# LED_Driver.net
KiCad netlist of a schematic drawn in Altium Designer
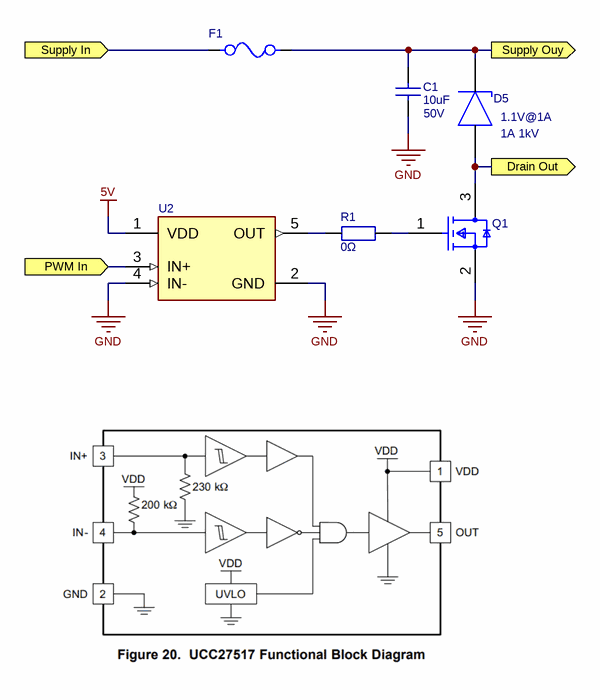
[diagram p0: LED Driver.SchDoc]

(export (version "E")
  (design (tool "Eeschema 10.0.6"))
  (components
    (comp (ref "C1")
      (value "10uF")
      (footprint "CAPC3225X20N")
      (fields (field (name "RATING") "50V"))
      (libsource (lib "SchematicLibrary") (part "SMD_Cap"))
    )
    (comp (ref "D5")
      (value "1.1V@1A")
      (footprint "sod-123FL")
      (description "1A Independent Type 1kV 1.1V@1A SOD-123FL Diodes")
      (fields (field (name "MPN") "SM4007PL") (field (name "RATING") "1A 1kV"))
      (libsource (lib "Miscellaneous Devices") (part "d386f69c7d770905792c16b93fa31a7"))
    )
    (comp (ref "F1")
      (value "~")
      (footprint "FP-0685T-IPC_C")
      (description "FUSE 3.0A 63VAC/DC SLOW 1206")
      (fields (field (name "MPN") "0468003.NRHF"))
      (libsource (lib "Altium Content Vault") (part "5bcf9b9f640e542cf0359d10258e979"))
    )
    (comp (ref "Q1")
      (value "~")
      (footprint "SOT95P245X110-3N")
      (description "N-Channel 30V 5.7A 1.5V @ 250uA 26.5mΩ @ 5.7A,10V 1.4W SOT-23-3L MOSFET RoHS")
      (fields (field (name "MPN") "AO3400A") (field (name "MANUFACTURER") "Alpha & Omega Semicon"))
      (libsource (lib "RedakoJLC") (part "AO3400A"))
    )
    (comp (ref "R1")
      (value "0Ω")
      (footprint "RESC1005X04N")
      (libsource (lib "SchematicLibrary") (part "Res"))
    )
    (comp (ref "U2")
      (value "~")
      (footprint "FP-DBV0005A-MFG")
      (description "IC GATE DVR LOW SIDE 1CH SOT23-5")
      (fields (field (name "MANUFACTURER") "Texas Instruments") (field (name "MPN") "UCC27517DBVR"))
      (libsource (lib "Altium Content Vault") (part "afd9589cfc2bb1d34802c7f90470f96"))
    )
  )
  (nets
    (net (code "1") (name "/Drain Out") (class "Default")
      (node (ref "D5") (pin "1") (pinfunction "A_1") (pintype "passive"))
      (node (ref "Q1") (pin "3") (pinfunction "D_3") (pintype "passive"))
    )
    (net (code "2") (name "/PWM In") (class "Default")
      (node (ref "U2") (pin "3") (pinfunction "IN+_3") (pintype "input"))
    )
    (net (code "3") (name "/Supply In") (class "Default")
      (node (ref "F1") (pin "1") (pinfunction "1_1") (pintype "passive"))
    )
    (net (code "4") (name "/Supply Ouy") (class "Default")
      (node (ref "C1") (pin "2") (pintype "passive"))
      (node (ref "D5") (pin "2") (pinfunction "C_2") (pintype "passive"))
      (node (ref "F1") (pin "2") (pinfunction "2_2") (pintype "passive"))
    )
    (net (code "5") (name "5V") (class "Default")
      (node (ref "U2") (pin "1") (pinfunction "VDD_1") (pintype "power_in"))
    )
    (net (code "6") (name "GND") (class "Default")
      (node (ref "C1") (pin "1") (pintype "passive"))
      (node (ref "Q1") (pin "2") (pinfunction "S_2") (pintype "passive"))
      (node (ref "U2") (pin "2") (pinfunction "GND_2") (pintype "power_in"))
      (node (ref "U2") (pin "4") (pinfunction "IN-_4") (pintype "input"))
    )
    (net (code "7") (name "Net-(Q1-G)") (class "Default")
      (node (ref "Q1") (pin "1") (pinfunction "G_1") (pintype "passive"))
      (node (ref "R1") (pin "2") (pintype "passive"))
    )
    (net (code "8") (name "Net-(U2-OUT)") (class "Default")
      (node (ref "R1") (pin "1") (pintype "passive"))
      (node (ref "U2") (pin "5") (pinfunction "OUT_5") (pintype "output"))
    )
  )
)
